# Base_Board_RevC.net
KiCad netlist of a schematic drawn in EAGLE
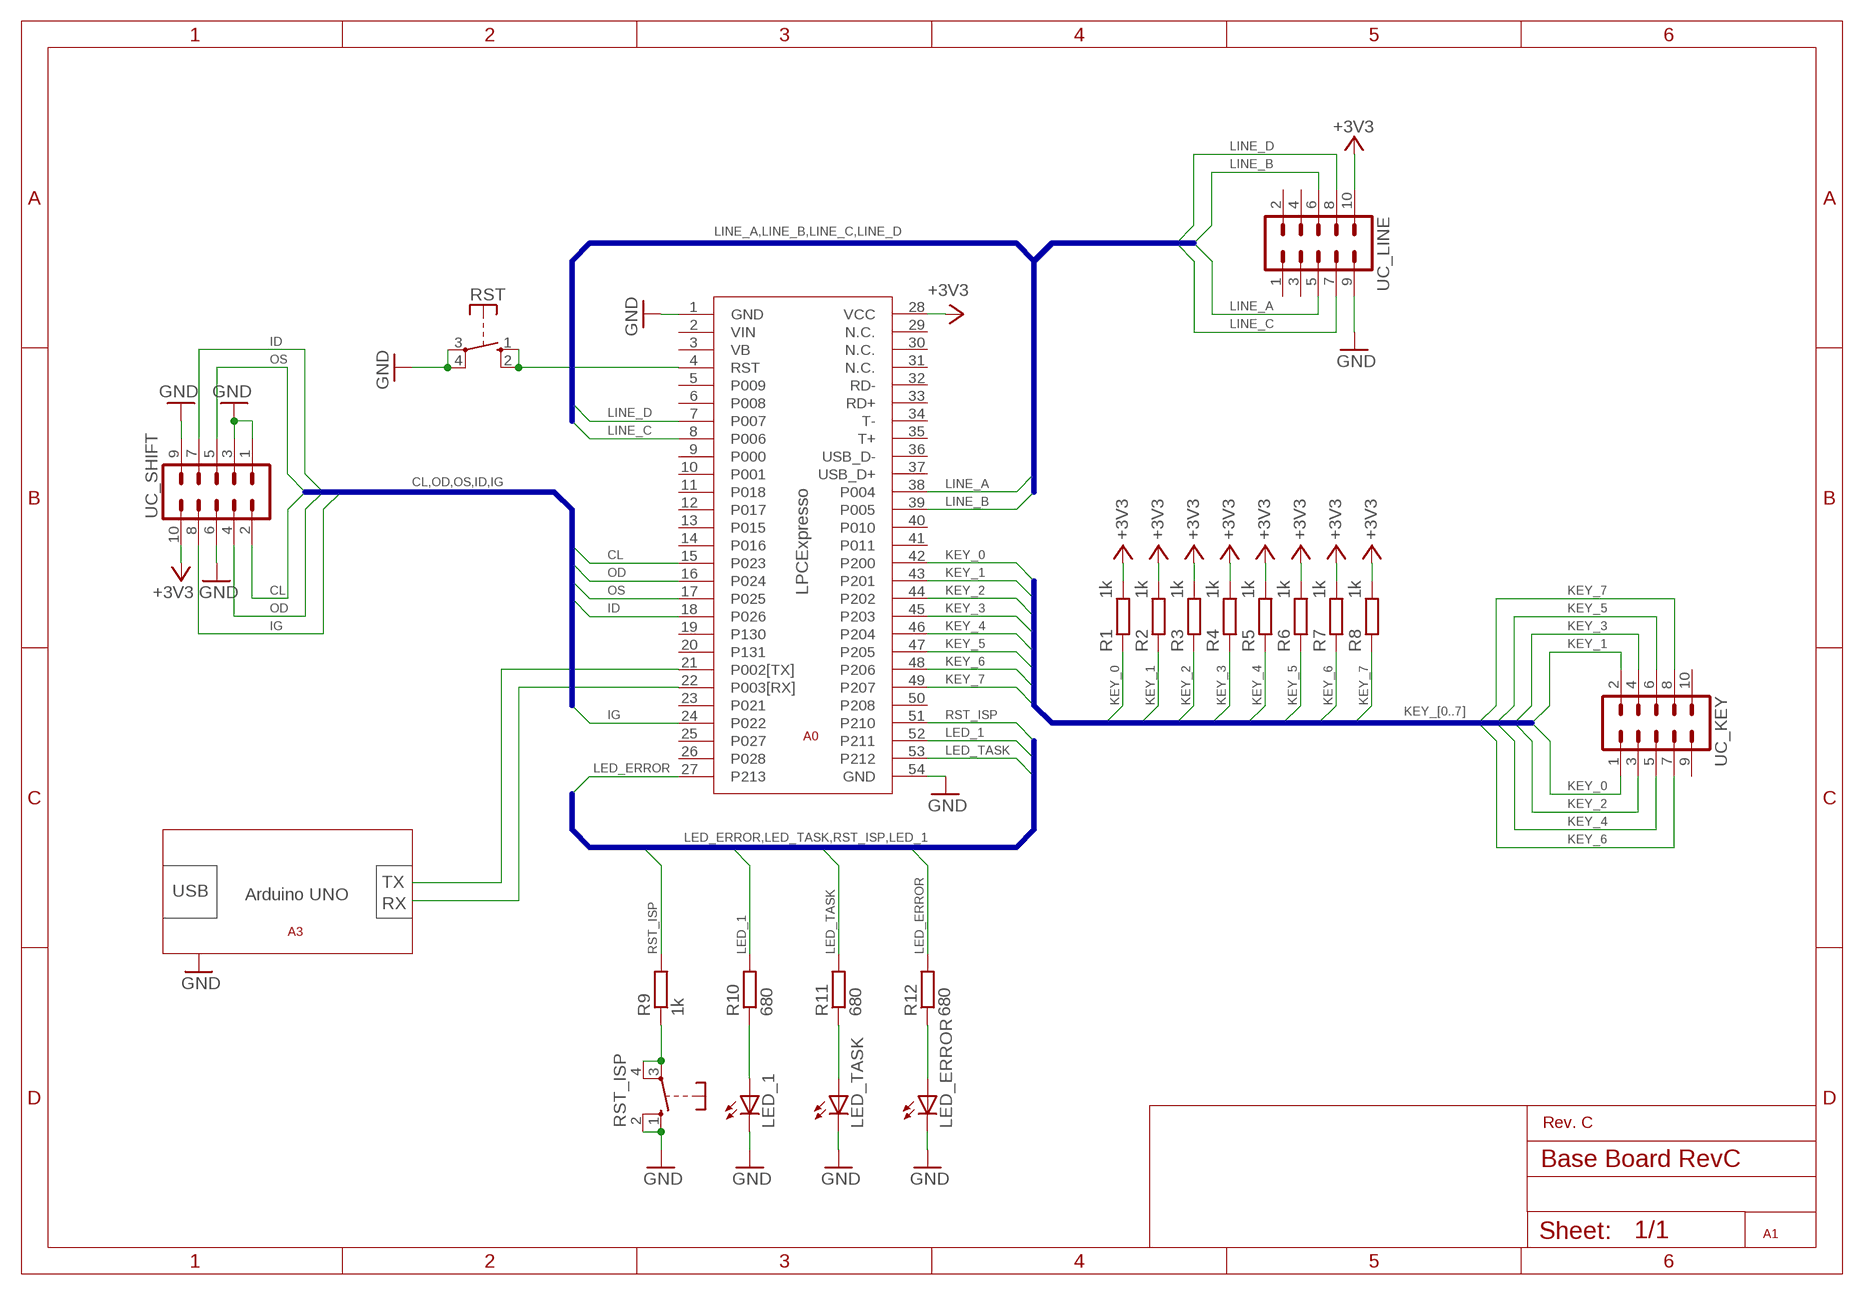
[diagram p0: schematic, sheet 1]

(export (version "E")
  (design (tool "Eeschema 10.0.6"))
  (components
    (comp (ref "LED_1")
      (value "LED5MM")
      (footprint "eagle-import:LED5MM")
      (libsource (lib "eagle-import") (part "LED5MM"))
    )
    (comp (ref "LED_ERROR")
      (value "LED5MM")
      (footprint "eagle-import:LED5MM")
      (libsource (lib "eagle-import") (part "LED5MM"))
    )
    (comp (ref "LED_TASK")
      (value "LED5MM")
      (footprint "eagle-import:LED5MM")
      (libsource (lib "eagle-import") (part "LED5MM"))
    )
    (comp (ref "R1")
      (value "1k")
      (footprint "eagle-import:0204_5")
      (libsource (lib "eagle-import") (part "R-EU_0204/5"))
    )
    (comp (ref "R2")
      (value "1k")
      (footprint "eagle-import:0204_5")
      (libsource (lib "eagle-import") (part "R-EU_0204/5"))
    )
    (comp (ref "R3")
      (value "1k")
      (footprint "eagle-import:0204_5")
      (libsource (lib "eagle-import") (part "R-EU_0204/5"))
    )
    (comp (ref "R4")
      (value "1k")
      (footprint "eagle-import:0204_5")
      (libsource (lib "eagle-import") (part "R-EU_0204/5"))
    )
    (comp (ref "R5")
      (value "1k")
      (footprint "eagle-import:0204_5")
      (libsource (lib "eagle-import") (part "R-EU_0204/5"))
    )
    (comp (ref "R6")
      (value "1k")
      (footprint "eagle-import:0204_5")
      (libsource (lib "eagle-import") (part "R-EU_0204/5"))
    )
    (comp (ref "R7")
      (value "1k")
      (footprint "eagle-import:0204_5")
      (libsource (lib "eagle-import") (part "R-EU_0204/5"))
    )
    (comp (ref "R8")
      (value "1k")
      (footprint "eagle-import:0204_5")
      (libsource (lib "eagle-import") (part "R-EU_0204/5"))
    )
    (comp (ref "R9")
      (value "1k")
      (footprint "eagle-import:0204_5")
      (libsource (lib "eagle-import") (part "R-EU_0204/5"))
    )
    (comp (ref "R10")
      (value "680")
      (footprint "eagle-import:0204_5")
      (libsource (lib "eagle-import") (part "R-EU_0204/5"))
    )
    (comp (ref "R11")
      (value "680")
      (footprint "eagle-import:0204_5")
      (libsource (lib "eagle-import") (part "R-EU_0204/5"))
    )
    (comp (ref "R12")
      (value "680")
      (footprint "eagle-import:0204_5")
      (libsource (lib "eagle-import") (part "R-EU_0204/5"))
    )
    (comp (ref "RST")
      (value "DT6")
      (footprint "eagle-import:DT6")
      (libsource (lib "eagle-import") (part "DT6"))
    )
    (comp (ref "RST_ISP")
      (value "DT6")
      (footprint "eagle-import:DT6")
      (libsource (lib "eagle-import") (part "DT6"))
    )
    (comp (ref "U$1")
      (value "LPCEXPRESSO")
      (footprint "eagle-import:LPCEXPRESSO")
      (libsource (lib "eagle-import") (part "LPCEXPRESSO"))
    )
    (comp (ref "UC_KEY")
      (value "ML10")
      (footprint "eagle-import:ML10")
      (libsource (lib "eagle-import") (part "ML10"))
    )
    (comp (ref "UC_LINE")
      (value "ML10")
      (footprint "eagle-import:ML10")
      (libsource (lib "eagle-import") (part "ML10"))
    )
    (comp (ref "UC_SHIFT")
      (value "ML10")
      (footprint "eagle-import:ML10")
      (libsource (lib "eagle-import") (part "ML10"))
    )
  )
  (nets
    (net (code "1") (name "+3V3") (class "Default")
      (node (ref "R1") (pin "1") (pinfunction "1_1") (pintype "passive"))
      (node (ref "R2") (pin "1") (pinfunction "1_1") (pintype "passive"))
      (node (ref "R3") (pin "1") (pinfunction "1_1") (pintype "passive"))
      (node (ref "R4") (pin "1") (pinfunction "1_1") (pintype "passive"))
      (node (ref "R5") (pin "1") (pinfunction "1_1") (pintype "passive"))
      (node (ref "R6") (pin "1") (pinfunction "1_1") (pintype "passive"))
      (node (ref "R7") (pin "1") (pinfunction "1_1") (pintype "passive"))
      (node (ref "R8") (pin "1") (pinfunction "1_1") (pintype "passive"))
      (node (ref "U$1") (pin "28") (pinfunction "VCC_28") (pintype "power_in"))
      (node (ref "UC_LINE") (pin "10") (pinfunction "10_10") (pintype "passive"))
      (node (ref "UC_SHIFT") (pin "10") (pinfunction "10_10") (pintype "passive"))
    )
    (net (code "2") (name "/CL") (class "Default")
      (node (ref "U$1") (pin "15") (pinfunction "P023_15") (pintype "bidirectional"))
      (node (ref "UC_SHIFT") (pin "2") (pinfunction "2_2") (pintype "passive"))
    )
    (net (code "3") (name "/ID") (class "Default")
      (node (ref "U$1") (pin "18") (pinfunction "P026_18") (pintype "bidirectional"))
      (node (ref "UC_SHIFT") (pin "7") (pinfunction "7_7") (pintype "passive"))
    )
    (net (code "4") (name "/IG") (class "Default")
      (node (ref "U$1") (pin "24") (pinfunction "P022_24") (pintype "bidirectional"))
      (node (ref "UC_SHIFT") (pin "8") (pinfunction "8_8") (pintype "passive"))
    )
    (net (code "5") (name "/KEY_0") (class "Default")
      (node (ref "R1") (pin "2") (pinfunction "2_2") (pintype "passive"))
      (node (ref "U$1") (pin "42") (pinfunction "P200_42") (pintype "bidirectional"))
      (node (ref "UC_KEY") (pin "1") (pinfunction "1_1") (pintype "passive"))
    )
    (net (code "6") (name "/KEY_1") (class "Default")
      (node (ref "R2") (pin "2") (pinfunction "2_2") (pintype "passive"))
      (node (ref "U$1") (pin "43") (pinfunction "P201_43") (pintype "bidirectional"))
      (node (ref "UC_KEY") (pin "2") (pinfunction "2_2") (pintype "passive"))
    )
    (net (code "7") (name "/KEY_2") (class "Default")
      (node (ref "R3") (pin "2") (pinfunction "2_2") (pintype "passive"))
      (node (ref "U$1") (pin "44") (pinfunction "P202_44") (pintype "bidirectional"))
      (node (ref "UC_KEY") (pin "3") (pinfunction "3_3") (pintype "passive"))
    )
    (net (code "8") (name "/KEY_3") (class "Default")
      (node (ref "R4") (pin "2") (pinfunction "2_2") (pintype "passive"))
      (node (ref "U$1") (pin "45") (pinfunction "P203_45") (pintype "bidirectional"))
      (node (ref "UC_KEY") (pin "4") (pinfunction "4_4") (pintype "passive"))
    )
    (net (code "9") (name "/KEY_4") (class "Default")
      (node (ref "R5") (pin "2") (pinfunction "2_2") (pintype "passive"))
      (node (ref "U$1") (pin "46") (pinfunction "P204_46") (pintype "bidirectional"))
      (node (ref "UC_KEY") (pin "5") (pinfunction "5_5") (pintype "passive"))
    )
    (net (code "10") (name "/KEY_5") (class "Default")
      (node (ref "R6") (pin "2") (pinfunction "2_2") (pintype "passive"))
      (node (ref "U$1") (pin "47") (pinfunction "P205_47") (pintype "bidirectional"))
      (node (ref "UC_KEY") (pin "6") (pinfunction "6_6") (pintype "passive"))
    )
    (net (code "11") (name "/KEY_6") (class "Default")
      (node (ref "R7") (pin "2") (pinfunction "2_2") (pintype "passive"))
      (node (ref "U$1") (pin "48") (pinfunction "P206_48") (pintype "bidirectional"))
      (node (ref "UC_KEY") (pin "7") (pinfunction "7_7") (pintype "passive"))
    )
    (net (code "12") (name "/KEY_7") (class "Default")
      (node (ref "R8") (pin "2") (pinfunction "2_2") (pintype "passive"))
      (node (ref "U$1") (pin "49") (pinfunction "P207_49") (pintype "bidirectional"))
      (node (ref "UC_KEY") (pin "8") (pinfunction "8_8") (pintype "passive"))
    )
    (net (code "14") (name "/LED_1") (class "Default")
      (node (ref "R10") (pin "2") (pinfunction "2_2") (pintype "passive"))
      (node (ref "U$1") (pin "52") (pinfunction "P211_52") (pintype "bidirectional"))
    )
    (net (code "15") (name "/LED_ERROR") (class "Default")
      (node (ref "R12") (pin "2") (pinfunction "2_2") (pintype "passive"))
      (node (ref "U$1") (pin "27") (pinfunction "P213_27") (pintype "bidirectional"))
    )
    (net (code "16") (name "/LED_TASK") (class "Default")
      (node (ref "R11") (pin "2") (pinfunction "2_2") (pintype "passive"))
      (node (ref "U$1") (pin "53") (pinfunction "P212_53") (pintype "bidirectional"))
    )
    (net (code "17") (name "/LINE_A") (class "Default")
      (node (ref "U$1") (pin "38") (pinfunction "P004_38") (pintype "bidirectional"))
      (node (ref "UC_LINE") (pin "5") (pinfunction "5_5") (pintype "passive"))
    )
    (net (code "18") (name "/LINE_B") (class "Default")
      (node (ref "U$1") (pin "39") (pinfunction "P005_39") (pintype "bidirectional"))
      (node (ref "UC_LINE") (pin "6") (pinfunction "6_6") (pintype "passive"))
    )
    (net (code "19") (name "/LINE_C") (class "Default")
      (node (ref "U$1") (pin "8") (pinfunction "P006_8") (pintype "bidirectional"))
      (node (ref "UC_LINE") (pin "7") (pinfunction "7_7") (pintype "passive"))
    )
    (net (code "20") (name "/LINE_D") (class "Default")
      (node (ref "U$1") (pin "7") (pinfunction "P007_7") (pintype "bidirectional"))
      (node (ref "UC_LINE") (pin "8") (pinfunction "8_8") (pintype "passive"))
    )
    (net (code "21") (name "/OD") (class "Default")
      (node (ref "U$1") (pin "16") (pinfunction "P024_16") (pintype "bidirectional"))
      (node (ref "UC_SHIFT") (pin "4") (pinfunction "4_4") (pintype "passive"))
    )
    (net (code "22") (name "/OS") (class "Default")
      (node (ref "U$1") (pin "17") (pinfunction "P025_17") (pintype "bidirectional"))
      (node (ref "UC_SHIFT") (pin "5") (pinfunction "5_5") (pintype "passive"))
    )
    (net (code "23") (name "/RST_ISP") (class "Default")
      (node (ref "R9") (pin "2") (pinfunction "2_2") (pintype "passive"))
      (node (ref "U$1") (pin "51") (pinfunction "P210_51") (pintype "bidirectional"))
    )
    (net (code "24") (name "/VB") (class "Default")
      (node (ref "U$1") (pin "3") (pinfunction "VB_3") (pintype "power_in"))
    )
    (net (code "28") (name "GND") (class "Default")
      (node (ref "LED_1") (pin "K") (pinfunction "C_K") (pintype "passive"))
      (node (ref "LED_ERROR") (pin "K") (pinfunction "C_K") (pintype "passive"))
      (node (ref "LED_TASK") (pin "K") (pinfunction "C_K") (pintype "passive"))
      (node (ref "RST") (pin "3") (pinfunction "P_3") (pintype "passive"))
      (node (ref "RST") (pin "4") (pinfunction "P_4") (pintype "passive"))
      (node (ref "RST_ISP") (pin "1") (pinfunction "S_1") (pintype "passive"))
      (node (ref "RST_ISP") (pin "2") (pinfunction "S_2") (pintype "passive"))
      (node (ref "U$1") (pin "1") (pinfunction "GND_1") (pintype "power_in"))
      (node (ref "U$1") (pin "54") (pinfunction "GND_54") (pintype "power_in"))
      (node (ref "UC_LINE") (pin "9") (pinfunction "9_9") (pintype "passive"))
      (node (ref "UC_SHIFT") (pin "1") (pinfunction "1_1") (pintype "passive"))
      (node (ref "UC_SHIFT") (pin "3") (pinfunction "3_3") (pintype "passive"))
      (node (ref "UC_SHIFT") (pin "6") (pinfunction "6_6") (pintype "passive"))
      (node (ref "UC_SHIFT") (pin "9") (pinfunction "9_9") (pintype "passive"))
    )
    (net (code "29") (name "Net-(LED_1-PadA)") (class "Default")
      (node (ref "LED_1") (pin "A") (pinfunction "A_A") (pintype "passive"))
      (node (ref "R10") (pin "1") (pinfunction "1_1") (pintype "passive"))
    )
    (net (code "30") (name "Net-(LED_ERROR-PadA)") (class "Default")
      (node (ref "LED_ERROR") (pin "A") (pinfunction "A_A") (pintype "passive"))
      (node (ref "R12") (pin "1") (pinfunction "1_1") (pintype "passive"))
    )
    (net (code "31") (name "Net-(LED_TASK-PadA)") (class "Default")
      (node (ref "LED_TASK") (pin "A") (pinfunction "A_A") (pintype "passive"))
      (node (ref "R11") (pin "1") (pinfunction "1_1") (pintype "passive"))
    )
    (net (code "32") (name "Net-(R9-Pad1)") (class "Default")
      (node (ref "R9") (pin "1") (pinfunction "1_1") (pintype "passive"))
      (node (ref "RST_ISP") (pin "3") (pinfunction "P_3") (pintype "passive"))
      (node (ref "RST_ISP") (pin "4") (pinfunction "P_4") (pintype "passive"))
    )
    (net (code "33") (name "Net-(U$1-RST)") (class "Default")
      (node (ref "RST") (pin "1") (pinfunction "S_1") (pintype "passive"))
      (node (ref "RST") (pin "2") (pinfunction "S_2") (pintype "passive"))
      (node (ref "U$1") (pin "4") (pinfunction "RST_4") (pintype "bidirectional"))
    )
    (net (code "34") (name "unconnected-(U$1-N.C.-Pad29)") (class "Default")
      (node (ref "U$1") (pin "29") (pinfunction "N.C._29") (pintype "no_connect"))
    )
    (net (code "35") (name "unconnected-(U$1-N.C.-Pad30)") (class "Default")
      (node (ref "U$1") (pin "30") (pinfunction "N.C._30") (pintype "no_connect"))
    )
    (net (code "36") (name "unconnected-(U$1-N.C.-Pad31)") (class "Default")
      (node (ref "U$1") (pin "31") (pinfunction "N.C._31") (pintype "no_connect"))
    )
    (net (code "37") (name "unconnected-(U$1-P000-Pad9)") (class "Default")
      (node (ref "U$1") (pin "9") (pinfunction "P000_9") (pintype "bidirectional"))
    )
    (net (code "38") (name "unconnected-(U$1-P001-Pad10)") (class "Default")
      (node (ref "U$1") (pin "10") (pinfunction "P001_10") (pintype "bidirectional"))
    )
    (net (code "39") (name "unconnected-(U$1-P002[TX]-Pad21)") (class "Default")
      (node (ref "U$1") (pin "21") (pinfunction "P002[TX]_21") (pintype "bidirectional"))
    )
    (net (code "40") (name "unconnected-(U$1-P003[RX]-Pad22)") (class "Default")
      (node (ref "U$1") (pin "22") (pinfunction "P003[RX]_22") (pintype "bidirectional"))
    )
    (net (code "41") (name "unconnected-(U$1-P008-Pad6)") (class "Default")
      (node (ref "U$1") (pin "6") (pinfunction "P008_6") (pintype "bidirectional"))
    )
    (net (code "42") (name "unconnected-(U$1-P009-Pad5)") (class "Default")
      (node (ref "U$1") (pin "5") (pinfunction "P009_5") (pintype "bidirectional"))
    )
    (net (code "43") (name "unconnected-(U$1-P010-Pad40)") (class "Default")
      (node (ref "U$1") (pin "40") (pinfunction "P010_40") (pintype "bidirectional"))
    )
    (net (code "44") (name "unconnected-(U$1-P011-Pad41)") (class "Default")
      (node (ref "U$1") (pin "41") (pinfunction "P011_41") (pintype "bidirectional"))
    )
    (net (code "45") (name "unconnected-(U$1-P015-Pad13)") (class "Default")
      (node (ref "U$1") (pin "13") (pinfunction "P015_13") (pintype "bidirectional"))
    )
    (net (code "46") (name "unconnected-(U$1-P016-Pad14)") (class "Default")
      (node (ref "U$1") (pin "14") (pinfunction "P016_14") (pintype "bidirectional"))
    )
    (net (code "47") (name "unconnected-(U$1-P017-Pad12)") (class "Default")
      (node (ref "U$1") (pin "12") (pinfunction "P017_12") (pintype "bidirectional"))
    )
    (net (code "48") (name "unconnected-(U$1-P018-Pad11)") (class "Default")
      (node (ref "U$1") (pin "11") (pinfunction "P018_11") (pintype "bidirectional"))
    )
    (net (code "49") (name "unconnected-(U$1-P021-Pad23)") (class "Default")
      (node (ref "U$1") (pin "23") (pinfunction "P021_23") (pintype "bidirectional"))
    )
    (net (code "50") (name "unconnected-(U$1-P027-Pad25)") (class "Default")
      (node (ref "U$1") (pin "25") (pinfunction "P027_25") (pintype "bidirectional"))
    )
    (net (code "51") (name "unconnected-(U$1-P028-Pad26)") (class "Default")
      (node (ref "U$1") (pin "26") (pinfunction "P028_26") (pintype "bidirectional"))
    )
    (net (code "52") (name "unconnected-(U$1-P130-Pad19)") (class "Default")
      (node (ref "U$1") (pin "19") (pinfunction "P130_19") (pintype "bidirectional"))
    )
    (net (code "53") (name "unconnected-(U$1-P131-Pad20)") (class "Default")
      (node (ref "U$1") (pin "20") (pinfunction "P131_20") (pintype "bidirectional"))
    )
    (net (code "54") (name "unconnected-(U$1-P208-Pad50)") (class "Default")
      (node (ref "U$1") (pin "50") (pinfunction "P208_50") (pintype "bidirectional"))
    )
    (net (code "55") (name "unconnected-(U$1-RD+-Pad33)") (class "Default")
      (node (ref "U$1") (pin "33") (pinfunction "RD+_33") (pintype "bidirectional"))
    )
    (net (code "56") (name "unconnected-(U$1-RD--Pad32)") (class "Default")
      (node (ref "U$1") (pin "32") (pinfunction "RD-_32") (pintype "bidirectional"))
    )
    (net (code "57") (name "unconnected-(U$1-T+-Pad35)") (class "Default")
      (node (ref "U$1") (pin "35") (pinfunction "T+_35") (pintype "bidirectional"))
    )
    (net (code "58") (name "unconnected-(U$1-T--Pad34)") (class "Default")
      (node (ref "U$1") (pin "34") (pinfunction "T-_34") (pintype "bidirectional"))
    )
    (net (code "59") (name "unconnected-(U$1-USB_D+-Pad37)") (class "Default")
      (node (ref "U$1") (pin "37") (pinfunction "USB_D+_37") (pintype "bidirectional"))
    )
    (net (code "60") (name "unconnected-(U$1-USB_D--Pad36)") (class "Default")
      (node (ref "U$1") (pin "36") (pinfunction "USB_D-_36") (pintype "bidirectional"))
    )
    (net (code "61") (name "unconnected-(U$1-VIN-Pad2)") (class "Default")
      (node (ref "U$1") (pin "2") (pinfunction "VIN_2") (pintype "input"))
    )
    (net (code "62") (name "unconnected-(UC_KEY-Pad9)") (class "Default")
      (node (ref "UC_KEY") (pin "9") (pinfunction "9_9") (pintype "passive"))
    )
    (net (code "63") (name "unconnected-(UC_KEY-Pad10)") (class "Default")
      (node (ref "UC_KEY") (pin "10") (pinfunction "10_10") (pintype "passive"))
    )
    (net (code "64") (name "unconnected-(UC_LINE-Pad1)") (class "Default")
      (node (ref "UC_LINE") (pin "1") (pinfunction "1_1") (pintype "passive"))
    )
    (net (code "65") (name "unconnected-(UC_LINE-Pad2)") (class "Default")
      (node (ref "UC_LINE") (pin "2") (pinfunction "2_2") (pintype "passive"))
    )
    (net (code "66") (name "unconnected-(UC_LINE-Pad3)") (class "Default")
      (node (ref "UC_LINE") (pin "3") (pinfunction "3_3") (pintype "passive"))
    )
    (net (code "67") (name "unconnected-(UC_LINE-Pad4)") (class "Default")
      (node (ref "UC_LINE") (pin "4") (pinfunction "4_4") (pintype "passive"))
    )
  )
)
